# PROC106B_PMIC.net
KiCad netlist of a schematic drawn in Altium Designer
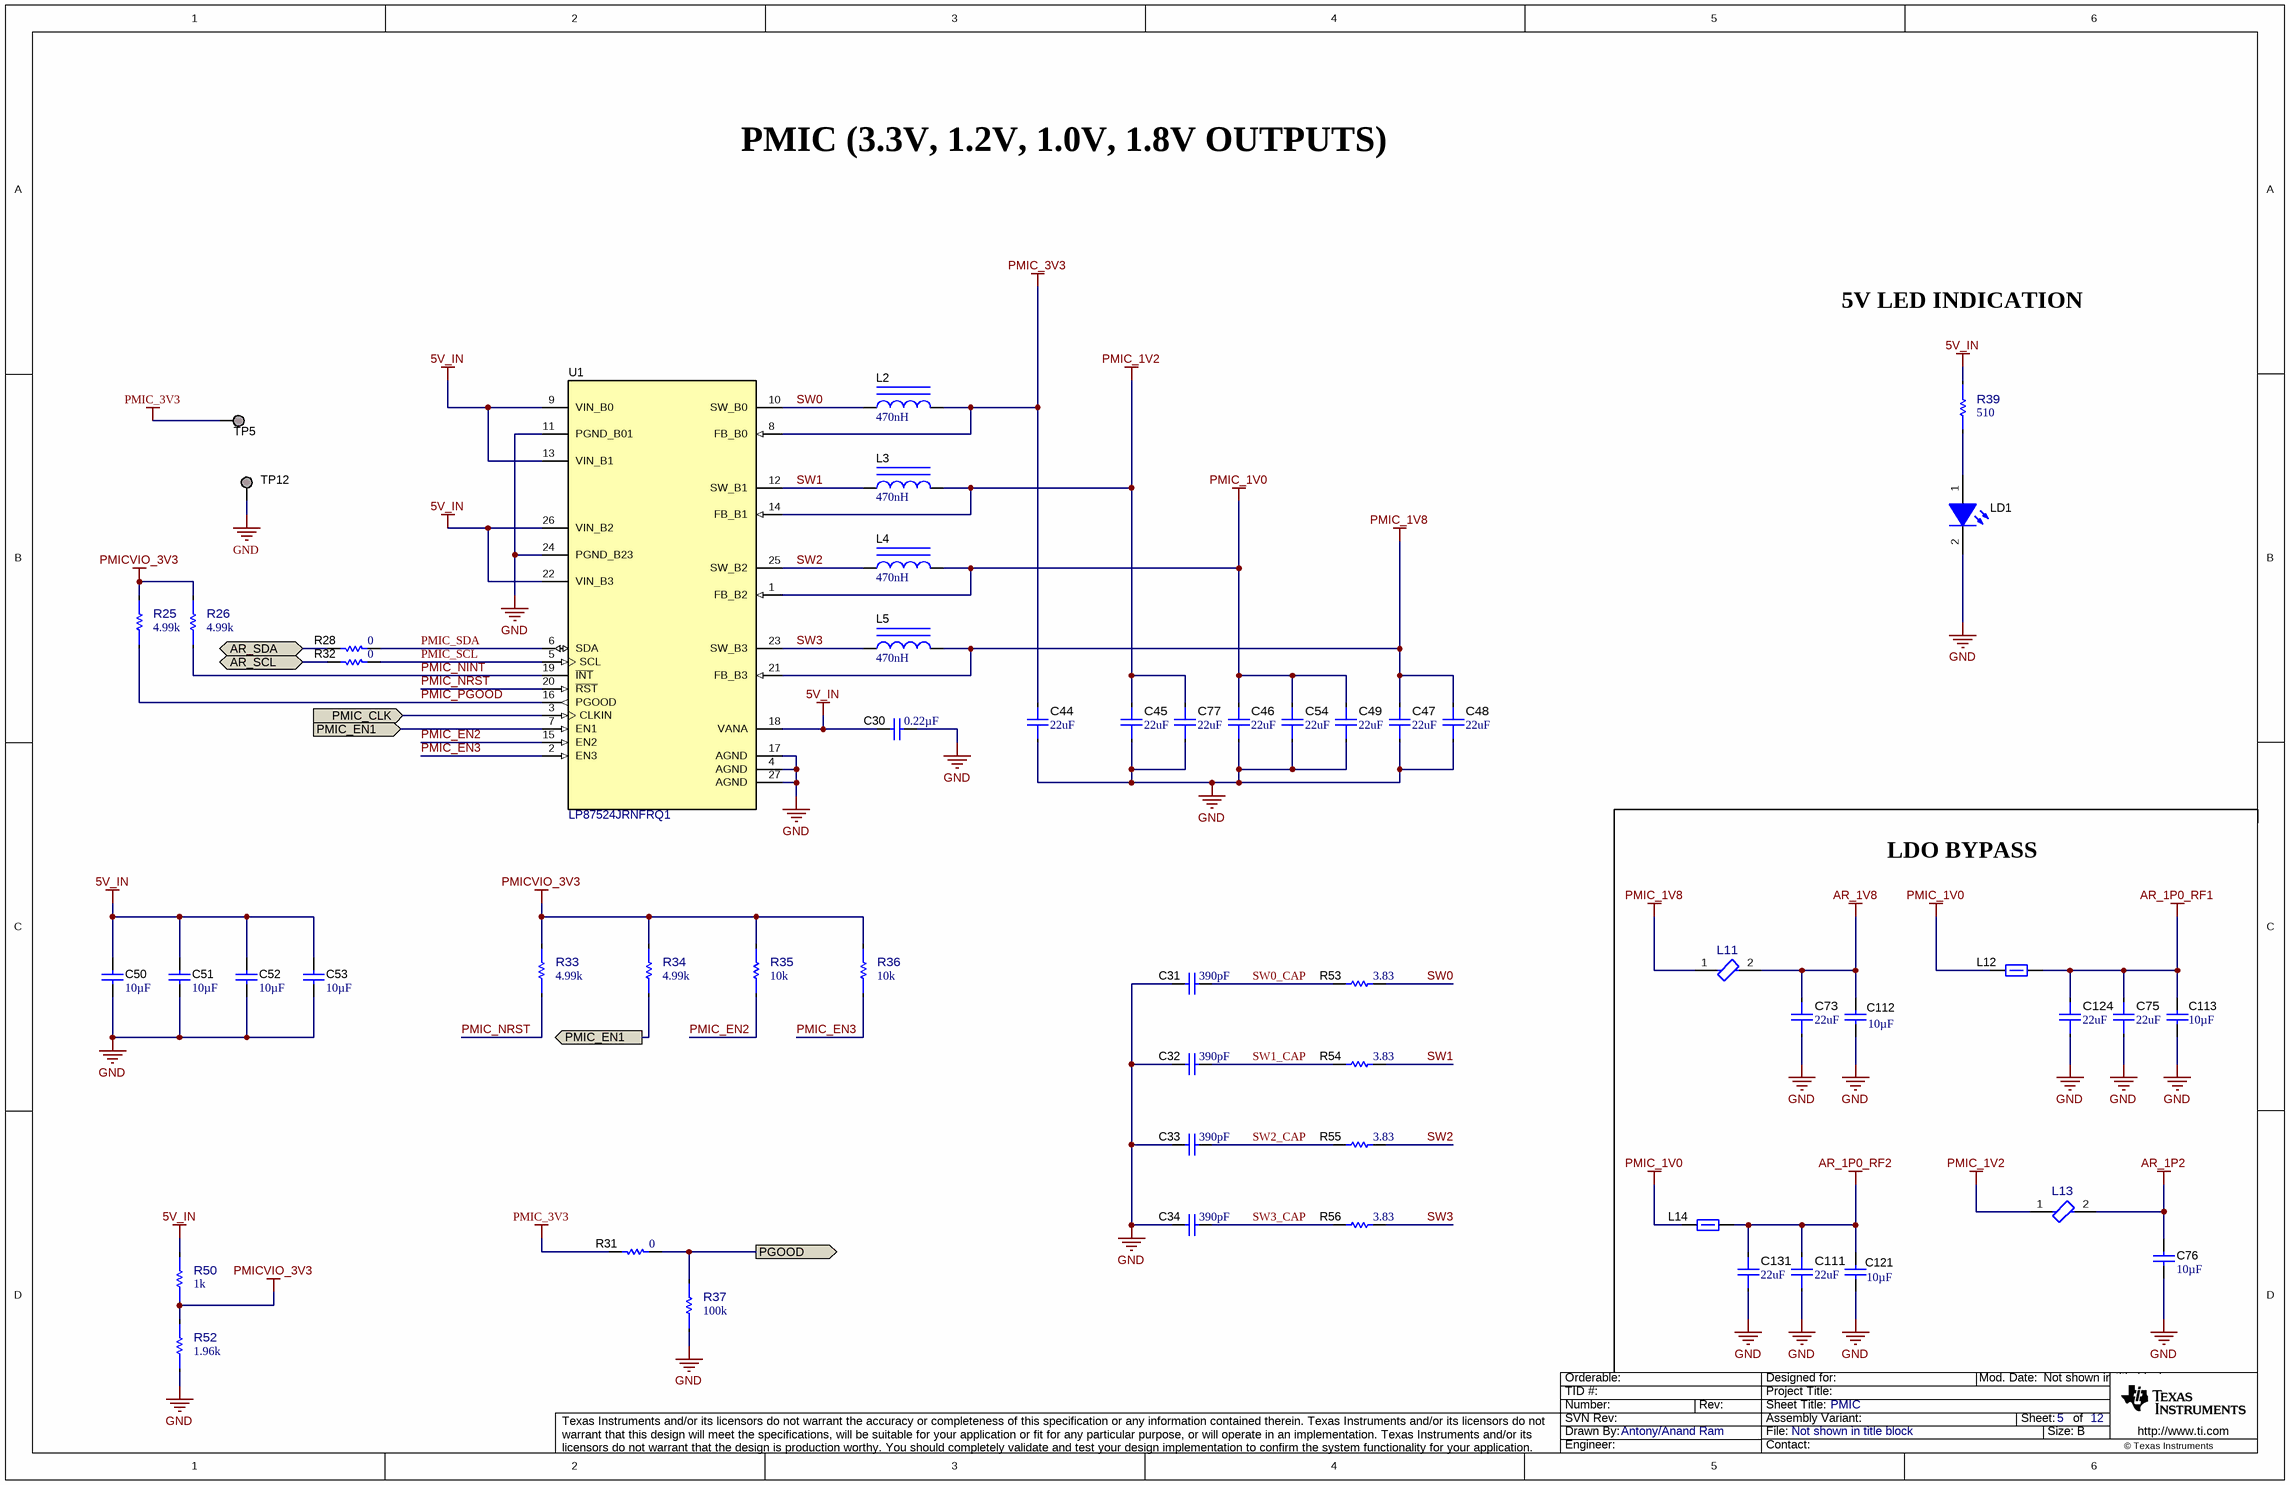
[diagram p0: PROC106B_PMIC.SchDoc]

(export (version "E")
  (design (tool "Eeschema 10.0.6"))
  (components
    (comp (ref "C30")
      (value "GCM155R71C224KE02D")
      (footprint "0402L")
      (description "CAP, CERM, 0.22 µF, 16 V,+/- 10%, X7R, AEC-Q200 Grade 1, 0402")
      (fields (field (name "MANUFACTURER") "MuRata") (field (name "VALUEDISPLAYED") "0.22µF"))
      (libsource (lib "Altium Vault - TI") (part "Capacitor"))
    )
    (comp (ref "C31")
      (value "CGA2B2C0G1H391J050BA")
      (footprint "0402L")
      (description "CAP, CERM, 390 pF, 50 V,+/- 5%, C0G/NP0, AEC-Q200 Grade 1, 0402")
      (fields (field (name "MANUFACTURER") "TDK") (field (name "VALUEDISPLAYED") "390pF"))
      (libsource (lib "Altium Vault - TI") (part "Capacitor"))
    )
    (comp (ref "C32")
      (value "CGA2B2C0G1H391J050BA")
      (footprint "0402L")
      (description "CAP, CERM, 390 pF, 50 V,+/- 5%, C0G/NP0, AEC-Q200 Grade 1, 0402")
      (fields (field (name "MANUFACTURER") "TDK") (field (name "VALUEDISPLAYED") "390pF"))
      (libsource (lib "Altium Vault - TI") (part "Capacitor"))
    )
    (comp (ref "C33")
      (value "CGA2B2C0G1H391J050BA")
      (footprint "0402L")
      (description "CAP, CERM, 390 pF, 50 V,+/- 5%, C0G/NP0, AEC-Q200 Grade 1, 0402")
      (fields (field (name "MANUFACTURER") "TDK") (field (name "VALUEDISPLAYED") "390pF"))
      (libsource (lib "Altium Vault - TI") (part "Capacitor"))
    )
    (comp (ref "C34")
      (value "CGA2B2C0G1H391J050BA")
      (footprint "0402L")
      (description "CAP, CERM, 390 pF, 50 V,+/- 5%, C0G/NP0, AEC-Q200 Grade 1, 0402")
      (fields (field (name "MANUFACTURER") "TDK") (field (name "VALUEDISPLAYED") "390pF"))
      (libsource (lib "Altium Vault - TI") (part "Capacitor"))
    )
    (comp (ref "C44")
      (value "CGA4J1X7T0J226M125AC")
      (footprint "FP-CGA4J1X7T0J226M125AC_0805-MFG")
      (description "22µF ±20% 6.3V Ceramic Capacitor X7T 0805 (2012 Metric)")
      (fields
        (field (name "DIGIKEY PART NUMBER") "445-CGA4J1X7T0J226M125ACCT-ND")
        (field (name "MOUSER PART NUMBER") "810-CGA4J1X7T0J226M1")
        (field (name "VALUEDISPLAYED") "22uF")
      )
      (libsource (lib "Altium Vault - TI") (part "SYM-CGA4J1X7T0J226M125AC"))
    )
    (comp (ref "C45")
      (value "CGA4J1X7T0J226M125AC")
      (footprint "FP-CGA4J1X7T0J226M125AC_0805-MFG")
      (description "22µF ±20% 6.3V Ceramic Capacitor X7T 0805 (2012 Metric)")
      (fields
        (field (name "DIGIKEY PART NUMBER") "445-CGA4J1X7T0J226M125ACCT-ND")
        (field (name "MOUSER PART NUMBER") "810-CGA4J1X7T0J226M1")
        (field (name "VALUEDISPLAYED") "22uF")
      )
      (libsource (lib "Altium Vault - TI") (part "SYM-CGA4J1X7T0J226M125AC"))
    )
    (comp (ref "C46")
      (value "CGA4J1X7T0J226M125AC")
      (footprint "FP-CGA4J1X7T0J226M125AC_0805-MFG")
      (description "22µF ±20% 6.3V Ceramic Capacitor X7T 0805 (2012 Metric)")
      (fields
        (field (name "DIGIKEY PART NUMBER") "445-CGA4J1X7T0J226M125ACCT-ND")
        (field (name "MOUSER PART NUMBER") "810-CGA4J1X7T0J226M1")
        (field (name "VALUEDISPLAYED") "22uF")
      )
      (libsource (lib "Altium Vault - TI") (part "SYM-CGA4J1X7T0J226M125AC"))
    )
    (comp (ref "C47")
      (value "CGA4J1X7T0J226M125AC")
      (footprint "FP-CGA4J1X7T0J226M125AC_0805-MFG")
      (description "22µF ±20% 6.3V Ceramic Capacitor X7T 0805 (2012 Metric)")
      (fields
        (field (name "DIGIKEY PART NUMBER") "445-CGA4J1X7T0J226M125ACCT-ND")
        (field (name "MOUSER PART NUMBER") "810-CGA4J1X7T0J226M1")
        (field (name "VALUEDISPLAYED") "22uF")
      )
      (libsource (lib "Altium Vault - TI") (part "SYM-CGA4J1X7T0J226M125AC"))
    )
    (comp (ref "C48")
      (value "CGA4J1X7T0J226M125AC")
      (footprint "FP-CGA4J1X7T0J226M125AC_0805-MFG")
      (description "22µF ±20% 6.3V Ceramic Capacitor X7T 0805 (2012 Metric)")
      (fields
        (field (name "DIGIKEY PART NUMBER") "445-CGA4J1X7T0J226M125ACCT-ND")
        (field (name "MOUSER PART NUMBER") "810-CGA4J1X7T0J226M1")
        (field (name "VALUEDISPLAYED") "22uF")
      )
      (libsource (lib "Altium Vault - TI") (part "SYM-CGA4J1X7T0J226M125AC"))
    )
    (comp (ref "C49")
      (value "CGA4J1X7T0J226M125AC")
      (footprint "FP-CGA4J1X7T0J226M125AC_0805-MFG")
      (description "22µF ±20% 6.3V Ceramic Capacitor X7T 0805 (2012 Metric)")
      (fields
        (field (name "DIGIKEY PART NUMBER") "445-CGA4J1X7T0J226M125ACCT-ND")
        (field (name "MOUSER PART NUMBER") "810-CGA4J1X7T0J226M1")
        (field (name "VALUEDISPLAYED") "22uF")
      )
      (libsource (lib "Altium Vault - TI") (part "SYM-CGA4J1X7T0J226M125AC"))
    )
    (comp (ref "C50")
      (value "GCM21BR71A106KE22L")
      (footprint "0805_HV1")
      (description "CAP, CERM, 10 uF, 10 V, +/- 10%, X7R, 0805")
      (fields
        (field (name "CAP_F") "10µF")
        (field (name "MANUFACTURER") "MuRata")
        (field (name "PUBLISHER") "Texas Instruments")
      )
      (libsource (lib "Altium Vault - TI") (part "Capacitor"))
    )
    (comp (ref "C51")
      (value "GCM21BR71A106KE22L")
      (footprint "0805_HV1")
      (description "CAP, CERM, 10 uF, 10 V, +/- 10%, X7R, 0805")
      (fields
        (field (name "CAP_F") "10µF")
        (field (name "MANUFACTURER") "MuRata")
        (field (name "PUBLISHER") "Texas Instruments")
      )
      (libsource (lib "Altium Vault - TI") (part "Capacitor"))
    )
    (comp (ref "C52")
      (value "GCM21BR71A106KE22L")
      (footprint "0805_HV1")
      (description "CAP, CERM, 10 uF, 10 V, +/- 10%, X7R, 0805")
      (fields
        (field (name "CAP_F") "10µF")
        (field (name "MANUFACTURER") "MuRata")
        (field (name "PUBLISHER") "Texas Instruments")
      )
      (libsource (lib "Altium Vault - TI") (part "Capacitor"))
    )
    (comp (ref "C53")
      (value "GCM21BR71A106KE22L")
      (footprint "0805_HV1")
      (description "CAP, CERM, 10 uF, 10 V, +/- 10%, X7R, 0805")
      (fields
        (field (name "CAP_F") "10µF")
        (field (name "MANUFACTURER") "MuRata")
        (field (name "PUBLISHER") "Texas Instruments")
      )
      (libsource (lib "Altium Vault - TI") (part "Capacitor"))
    )
    (comp (ref "C54")
      (value "CGA4J1X7T0J226M125AC")
      (footprint "FP-CGA4J1X7T0J226M125AC_0805-MFG")
      (description "22µF ±20% 6.3V Ceramic Capacitor X7T 0805 (2012 Metric)")
      (fields
        (field (name "DIGIKEY PART NUMBER") "445-CGA4J1X7T0J226M125ACCT-ND")
        (field (name "MOUSER PART NUMBER") "810-CGA4J1X7T0J226M1")
        (field (name "VALUEDISPLAYED") "22uF")
      )
      (libsource (lib "Altium Vault - TI") (part "SYM-CGA4J1X7T0J226M125AC"))
    )
    (comp (ref "C73")
      (value "CGA4J1X7T0J226M125AC")
      (footprint "FP-CGA4J1X7T0J226M125AC_0805-MFG")
      (description "22µF ±20% 6.3V Ceramic Capacitor X7T 0805 (2012 Metric)")
      (fields
        (field (name "DIGIKEY PART NUMBER") "445-CGA4J1X7T0J226M125ACCT-ND")
        (field (name "MOUSER PART NUMBER") "810-CGA4J1X7T0J226M1")
        (field (name "VALUEDISPLAYED") "22uF")
      )
      (libsource (lib "Altium Vault - TI") (part "SYM-CGA4J1X7T0J226M125AC"))
    )
    (comp (ref "C75")
      (value "CGA4J1X7T0J226M125AC")
      (footprint "FP-CGA4J1X7T0J226M125AC_0805-MFG")
      (description "22µF ±20% 6.3V Ceramic Capacitor X7T 0805 (2012 Metric)")
      (fields
        (field (name "DIGIKEY PART NUMBER") "445-CGA4J1X7T0J226M125ACCT-ND")
        (field (name "MOUSER PART NUMBER") "810-CGA4J1X7T0J226M1")
        (field (name "VALUEDISPLAYED") "22uF")
      )
      (libsource (lib "Altium Vault - TI") (part "SYM-CGA4J1X7T0J226M125AC"))
    )
    (comp (ref "C76")
      (value "GCM21BR71A106KE22L")
      (footprint "0805L")
      (description "CAP, CERM, 10 uF, 10 V, +/- 10%, X7R, 0805")
      (fields
        (field (name "CAP_F") "10µF")
        (field (name "MANUFACTURER") "MuRata")
        (field (name "PUBLISHER") "Texas Instruments")
      )
      (libsource (lib "Altium Vault - TI") (part "Capacitor"))
    )
    (comp (ref "C77")
      (value "CGA4J1X7T0J226M125AC")
      (footprint "FP-CGA4J1X7T0J226M125AC_0805-MFG")
      (description "22µF ±20% 6.3V Ceramic Capacitor X7T 0805 (2012 Metric)")
      (fields
        (field (name "DIGIKEY PART NUMBER") "445-CGA4J1X7T0J226M125ACCT-ND")
        (field (name "MOUSER PART NUMBER") "810-CGA4J1X7T0J226M1")
        (field (name "VALUEDISPLAYED") "22uF")
      )
      (libsource (lib "Altium Vault - TI") (part "SYM-CGA4J1X7T0J226M125AC"))
    )
    (comp (ref "C111")
      (value "CGA4J1X7T0J226M125AC")
      (footprint "FP-CGA4J1X7T0J226M125AC_0805-MFG")
      (description "22µF ±20% 6.3V Ceramic Capacitor X7T 0805 (2012 Metric)")
      (fields
        (field (name "DIGIKEY PART NUMBER") "445-CGA4J1X7T0J226M125ACCT-ND")
        (field (name "MOUSER PART NUMBER") "810-CGA4J1X7T0J226M1")
        (field (name "VALUEDISPLAYED") "22uF")
      )
      (libsource (lib "Altium Vault - TI") (part "SYM-CGA4J1X7T0J226M125AC"))
    )
    (comp (ref "C112")
      (value "GCM21BR71A106KE22L")
      (footprint "0805L")
      (description "CAP, CERM, 10 uF, 10 V, +/- 10%, X7R, 0805")
      (fields
        (field (name "CAP_F") "10µF")
        (field (name "MANUFACTURER") "MuRata")
        (field (name "PUBLISHER") "Texas Instruments")
      )
      (libsource (lib "Altium Vault - TI") (part "Capacitor"))
    )
    (comp (ref "C113")
      (value "GCM21BR71A106KE22L")
      (footprint "0805L")
      (description "CAP, CERM, 10 uF, 10 V, +/- 10%, X7R, 0805")
      (fields
        (field (name "CAP_F") "10µF")
        (field (name "MANUFACTURER") "MuRata")
        (field (name "PUBLISHER") "Texas Instruments")
      )
      (libsource (lib "Altium Vault - TI") (part "Capacitor"))
    )
    (comp (ref "C121")
      (value "GCM21BR71A106KE22L")
      (footprint "0805L")
      (description "CAP, CERM, 10 uF, 10 V, +/- 10%, X7R, 0805")
      (fields
        (field (name "CAP_F") "10µF")
        (field (name "MANUFACTURER") "MuRata")
        (field (name "PUBLISHER") "Texas Instruments")
      )
      (libsource (lib "Altium Vault - TI") (part "Capacitor"))
    )
    (comp (ref "C124")
      (value "CGA4J1X7T0J226M125AC")
      (footprint "FP-CGA4J1X7T0J226M125AC_0805-MFG")
      (description "22µF ±20% 6.3V Ceramic Capacitor X7T 0805 (2012 Metric)")
      (fields
        (field (name "DIGIKEY PART NUMBER") "445-CGA4J1X7T0J226M125ACCT-ND")
        (field (name "MOUSER PART NUMBER") "810-CGA4J1X7T0J226M1")
        (field (name "VALUEDISPLAYED") "22uF")
      )
      (libsource (lib "Altium Vault - TI") (part "SYM-CGA4J1X7T0J226M125AC"))
    )
    (comp (ref "C131")
      (value "CGA4J1X7T0J226M125AC")
      (footprint "FP-CGA4J1X7T0J226M125AC_0805-MFG")
      (description "22µF ±20% 6.3V Ceramic Capacitor X7T 0805 (2012 Metric)")
      (fields
        (field (name "DIGIKEY PART NUMBER") "445-CGA4J1X7T0J226M125ACCT-ND")
        (field (name "MOUSER PART NUMBER") "810-CGA4J1X7T0J226M1")
        (field (name "VALUEDISPLAYED") "22uF")
      )
      (libsource (lib "Altium Vault - TI") (part "SYM-CGA4J1X7T0J226M125AC"))
    )
    (comp (ref "L2")
      (value "DFE252012PD-R47M")
      (footprint "DFE252012P")
      (description "Inductor, Shielded, 470 nH, 4.7 A, 0.021 ohm, SMD")
      (fields
        (field (name "MANUFACTURER") "MuRata Toko")
        (field (name "VALUEDISPLAYED") "470nH")
        (field (name "PUBLISHER") "Texas Instruments")
      )
      (libsource (lib "Altium Vault - TI") (part "Inductor_Iron"))
    )
    (comp (ref "L3")
      (value "DFE252012PD-R47M")
      (footprint "DFE252012P")
      (description "Inductor, Shielded, 470 nH, 4.7 A, 0.021 ohm, SMD")
      (fields
        (field (name "MANUFACTURER") "MuRata Toko")
        (field (name "VALUEDISPLAYED") "470nH")
        (field (name "PUBLISHER") "Texas Instruments")
      )
      (libsource (lib "Altium Vault - TI") (part "Inductor_Iron"))
    )
    (comp (ref "L4")
      (value "DFE252012PD-R47M")
      (footprint "DFE252012P")
      (description "Inductor, Shielded, 470 nH, 4.7 A, 0.021 ohm, SMD")
      (fields
        (field (name "MANUFACTURER") "MuRata Toko")
        (field (name "VALUEDISPLAYED") "470nH")
        (field (name "PUBLISHER") "Texas Instruments")
      )
      (libsource (lib "Altium Vault - TI") (part "Inductor_Iron"))
    )
    (comp (ref "L5")
      (value "DFE252012PD-R47M")
      (footprint "DFE252012P")
      (description "Inductor, Shielded, 470 nH, 4.7 A, 0.021 ohm, SMD")
      (fields
        (field (name "MANUFACTURER") "MuRata Toko")
        (field (name "VALUEDISPLAYED") "470nH")
        (field (name "PUBLISHER") "Texas Instruments")
      )
      (libsource (lib "Altium Vault - TI") (part "Inductor_Iron"))
    )
    (comp (ref "L11")
      (value "MPZ2012S101ATD25")
      (footprint "FP-MPZ2012S101ATD25_0805-MFG")
      (description "100 Ohms @ 100MHz 1 Power Line Ferrite Bead 0805 (2012 Metric) 4A 20mOhm")
      (fields (field (name "MANUFACTURER") "TDK") (field (name "DIGIKEY PART NUMBER") "445-172903-1-ND"))
      (libsource (lib "Altium Vault - TI") (part "SYM-MPZ2012S101ATD25"))
    )
    (comp (ref "L12")
      (value "BLM18KG121TH1D")
      (footprint "0603_HV")
      (description "Ferrite Bead, 120 ohm @ 100 MHz, 1.9 A, 0603")
      (fields (field (name "MANUFACTURER") "MuRata"))
      (libsource (lib "Altium Vault - TI") (part "Ferrite_Bead"))
    )
    (comp (ref "L13")
      (value "MPZ2012S101ATD25")
      (footprint "FP-MPZ2012S101ATD25_0805-MFG")
      (description "100 Ohms @ 100MHz 1 Power Line Ferrite Bead 0805 (2012 Metric) 4A 20mOhm")
      (fields (field (name "MANUFACTURER") "TDK") (field (name "DIGIKEY PART NUMBER") "445-172903-1-ND"))
      (libsource (lib "Altium Vault - TI") (part "SYM-MPZ2012S101ATD25"))
    )
    (comp (ref "L14")
      (value "BLM18KG121TH1D")
      (footprint "0603_HV")
      (description "Ferrite Bead, 120 ohm @ 100 MHz, 1.9 A, 0603")
      (fields (field (name "MANUFACTURER") "MuRata"))
      (libsource (lib "Altium Vault - TI") (part "Ferrite_Bead"))
    )
    (comp (ref "LD1")
      (value "APHHS1005CGCK")
      (footprint "APHHS1005_Green")
      (description "LED, Green, SMD")
      (fields (field (name "MANUFACTURER") "Kingbright"))
      (libsource (lib "Altium Vault - TI") (part "LED"))
    )
    (comp (ref "R25")
      (value "4.99k")
      (footprint "FP-ERJ-1GNF4991C_0201-IPC_C")
      (description "4.99 kOhms ±1% 0.05W, 1/20W Chip Resistor 0201 (0603 Metric) Automotive AEC-Q200 Thick Film")
      (fields
        (field (name "MANUFACTURER") "Panasonic Electronic Components")
        (field (name "PARTNUMBER") "ERJ-1GNF4991C")
      )
      (libsource (lib "Altium Vault - TI") (part "SYM-ERJ-1GNF4991C"))
    )
    (comp (ref "R26")
      (value "4.99k")
      (footprint "FP-ERJ-1GNF4991C_0201-IPC_C")
      (description "4.99 kOhms ±1% 0.05W, 1/20W Chip Resistor 0201 (0603 Metric) Automotive AEC-Q200 Thick Film")
      (fields
        (field (name "MANUFACTURER") "Panasonic Electronic Components")
        (field (name "PARTNUMBER") "ERJ-1GNF4991C")
      )
      (libsource (lib "Altium Vault - TI") (part "SYM-ERJ-1GNF4991C"))
    )
    (comp (ref "R28")
      (value "ERJ-1GN0R00C")
      (footprint "0201L")
      (description "RES, 0, 5%, .05 W, AEC-Q200 Grade 0, 0201")
      (fields
        (field (name "MANUFACTURER") "Panasonic")
        (field (name "VALUEDISPLAYED") "0")
        (field (name "PUBLISHER") "Texas Instruments")
      )
      (libsource (lib "Altium Vault - TI") (part "Resistor"))
    )
    (comp (ref "R31")
      (value "ERJ-1GN0R00C")
      (footprint "0201L")
      (description "RES, 0, 5%, .05 W, AEC-Q200 Grade 0, 0201")
      (fields
        (field (name "MANUFACTURER") "Panasonic")
        (field (name "VALUEDISPLAYED") "0")
        (field (name "PUBLISHER") "Texas Instruments")
      )
      (libsource (lib "Altium Vault - TI") (part "Resistor"))
    )
    (comp (ref "R32")
      (value "ERJ-1GN0R00C")
      (footprint "0201L")
      (description "RES, 0, 5%, .05 W, AEC-Q200 Grade 0, 0201")
      (fields
        (field (name "MANUFACTURER") "Panasonic")
        (field (name "VALUEDISPLAYED") "0")
        (field (name "PUBLISHER") "Texas Instruments")
      )
      (libsource (lib "Altium Vault - TI") (part "Resistor"))
    )
    (comp (ref "R33")
      (value "4.99k")
      (footprint "FP-ERJ-1GNF4991C_0201-IPC_C")
      (description "4.99 kOhms ±1% 0.05W, 1/20W Chip Resistor 0201 (0603 Metric) Automotive AEC-Q200 Thick Film")
      (fields
        (field (name "MANUFACTURER") "Panasonic Electronic Components")
        (field (name "PARTNUMBER") "ERJ-1GNF4991C")
      )
      (libsource (lib "Altium Vault - TI") (part "SYM-ERJ-1GNF4991C"))
    )
    (comp (ref "R34")
      (value "4.99k")
      (footprint "FP-ERJ-1GNF4991C_0201-IPC_C")
      (description "4.99 kOhms ±1% 0.05W, 1/20W Chip Resistor 0201 (0603 Metric) Automotive AEC-Q200 Thick Film")
      (fields
        (field (name "MANUFACTURER") "Panasonic Electronic Components")
        (field (name "PARTNUMBER") "ERJ-1GNF4991C")
      )
      (libsource (lib "Altium Vault - TI") (part "SYM-ERJ-1GNF4991C"))
    )
    (comp (ref "R35")
      (value "10k")
      (footprint "FP-ERA-1AEB103C_0201-IPC_C")
      (description "RES SMD 10K OHM 0.1% 1/20W 0201")
      (fields (field (name "MANUFACTURER") "Panasonic") (field (name "PARTNUMBER") "ERA-1AEB103C"))
      (libsource (lib "Altium Vault - TI") (part "SYM-ERA-1AEB103C"))
    )
    (comp (ref "R36")
      (value "10k")
      (footprint "FP-ERA-1AEB103C_0201-IPC_C")
      (description "RES SMD 10K OHM 0.1% 1/20W 0201")
      (fields (field (name "MANUFACTURER") "Panasonic") (field (name "PARTNUMBER") "ERA-1AEB103C"))
      (libsource (lib "Altium Vault - TI") (part "SYM-ERA-1AEB103C"))
    )
    (comp (ref "R37")
      (value "100k")
      (footprint "FP-ERJ-1GNF1003C_0201-IPC_C")
      (description "100 kOhms ±1% 0.05W, 1/20W Chip Resistor 0201 (0603 Metric) Automotive AEC-Q200 Thick Film")
      (fields
        (field (name "MANUFACTURER") "Panasonic Electronic Components")
        (field (name "PARTNUMBER") "ERJ-1GNF1003C")
      )
      (libsource (lib "Altium Vault - TI") (part "SYM-ERJ-1GNF1003C"))
    )
    (comp (ref "R39")
      (value "510")
      (footprint "FP-ERJ-1GNJ511C_0201-IPC_C")
      (description "510 Ohms ±5% 0.05W, 1/20W Chip Resistor 0201 (0603 Metric) Automotive AEC-Q200 Thick Film")
      (fields
        (field (name "MANUFACTURER") "Panasonic Electronic Components")
        (field (name "PARTNUMBER") "ERJ-1GNJ511C")
      )
      (libsource (lib "Altium Vault - TI") (part "SYM-ERJ-1GNJ511C"))
    )
    (comp (ref "R50")
      (value "1k")
      (footprint "FP-ERJ-1GNJ102C_0201-IPC_C")
      (description "1 kOhms ±5% 0.05W, 1/20W Chip Resistor 0201 (0603 Metric) Automotive AEC-Q200 Thick Film")
      (fields
        (field (name "MANUFACTURER") "Panasonic Electronic Components")
        (field (name "PARTNUMBER") "ERJ-1GNJ102C")
      )
      (libsource (lib "Altium Vault - TI") (part "SYM-ERJ-1GNJ102C"))
    )
    (comp (ref "R52")
      (value "1.96k")
      (footprint "FP-ERJ-1GNF1961C_0201-IPC_C")
      (description "Res Thick Film 0201 1.96K Ohm 1% 1/20W 200ppm/C Molded SMD T/R")
      (fields (field (name "MANUFACTURER") "Panasonic") (field (name "PARTNUMBER") "ERJ-1GNF1961C"))
      (libsource (lib "Altium Vault - TI") (part "SYM-ERJ-1GNF1961C"))
    )
    (comp (ref "R53")
      (value "CRCW04023R83FKED")
      (footprint "0402L")
      (description "RES, 3.83, 1%, 0.063 W, AEC-Q200 Grade 0, 0402")
      (fields (field (name "MANUFACTURER") "Vishay-Dale") (field (name "VALUEDISPLAYED") "3.83"))
      (libsource (lib "Altium Vault - TI") (part "Resistor"))
    )
    (comp (ref "R54")
      (value "CRCW04023R83FKED")
      (footprint "0402L")
      (description "RES, 3.83, 1%, 0.063 W, AEC-Q200 Grade 0, 0402")
      (fields (field (name "MANUFACTURER") "Vishay-Dale") (field (name "VALUEDISPLAYED") "3.83"))
      (libsource (lib "Altium Vault - TI") (part "Resistor"))
    )
    (comp (ref "R55")
      (value "CRCW04023R83FKED")
      (footprint "0402L")
      (description "RES, 3.83, 1%, 0.063 W, AEC-Q200 Grade 0, 0402")
      (fields (field (name "MANUFACTURER") "Vishay-Dale") (field (name "VALUEDISPLAYED") "3.83"))
      (libsource (lib "Altium Vault - TI") (part "Resistor"))
    )
    (comp (ref "R56")
      (value "CRCW04023R83FKED")
      (footprint "0402L")
      (description "RES, 3.83, 1%, 0.063 W, AEC-Q200 Grade 0, 0402")
      (fields (field (name "MANUFACTURER") "Vishay-Dale") (field (name "VALUEDISPLAYED") "3.83"))
      (libsource (lib "Altium Vault - TI") (part "Resistor"))
    )
    (comp (ref "TP5")
      (value "TESTPOINT")
      (footprint "TP_25MIL-SMT")
      (description "TEST POINT.  No entry in BOM.")
      (libsource (lib "Altium Vault - TI") (part "TESTPOINT"))
    )
    (comp (ref "TP12")
      (value "TESTPOINT")
      (footprint "TP_VIA_060RND040")
      (description "TEST POINT.  No entry in BOM.")
      (libsource (lib "Altium Vault - TI") (part "TESTPOINT"))
    )
    (comp (ref "U1")
      (value "LP87524JRNFRQ1")
      (footprint "RNF0026C")
      (description "4-A + 2.5-A + Two 1.5-A Buck Converters With Integrated Switches, RNF0026C (VQFN-HR-26)")
      (fields
        (field (name "ALTERNATE PARTNUMBER") "LP87524JRNFTQ1")
        (field (name "MANUFACTURER") "Texas Instruments")
      )
      (libsource (lib "Altium Vault - TI") (part "LP87524"))
    )
  )
  (nets
    (net (code "1") (name "/AR_SCL") (class "Default")
      (node (ref "R32") (pin "1") (pinfunction "1_1") (pintype "passive"))
    )
    (net (code "2") (name "/AR_SDA") (class "Default")
      (node (ref "R28") (pin "1") (pinfunction "1_1") (pintype "passive"))
    )
    (net (code "3") (name "/PGOOD") (class "Default")
      (node (ref "R31") (pin "2") (pinfunction "2_2") (pintype "passive"))
      (node (ref "R37") (pin "2") (pinfunction "2_2") (pintype "passive"))
    )
    (net (code "4") (name "/PMIC_CLK") (class "Default")
      (node (ref "U1") (pin "3") (pinfunction "CLKIN_3") (pintype "input"))
    )
    (net (code "5") (name "/PMIC_EN1") (class "Default")
      (node (ref "R34") (pin "1") (pinfunction "1_1") (pintype "passive"))
      (node (ref "U1") (pin "7") (pinfunction "EN1_7") (pintype "input"))
    )
    (net (code "6") (name "/PMIC_EN2") (class "Default")
      (node (ref "R35") (pin "1") (pinfunction "1_1") (pintype "passive"))
      (node (ref "U1") (pin "15") (pinfunction "EN2_15") (pintype "input"))
    )
    (net (code "7") (name "/PMIC_EN3") (class "Default")
      (node (ref "R36") (pin "1") (pinfunction "1_1") (pintype "passive"))
      (node (ref "U1") (pin "2") (pinfunction "EN3_2") (pintype "input"))
    )
    (net (code "8") (name "/PMIC_NINT") (class "Default")
      (node (ref "R26") (pin "1") (pinfunction "1_1") (pintype "passive"))
      (node (ref "U1") (pin "19") (pinfunction "INT_19") (pintype "open_collector"))
    )
    (net (code "9") (name "/PMIC_NRST") (class "Default")
      (node (ref "R33") (pin "1") (pinfunction "1_1") (pintype "passive"))
      (node (ref "U1") (pin "20") (pinfunction "RST_20") (pintype "input"))
    )
    (net (code "10") (name "/PMIC_PGOOD") (class "Default")
      (node (ref "R25") (pin "1") (pinfunction "1_1") (pintype "passive"))
      (node (ref "U1") (pin "16") (pinfunction "PGOOD_16") (pintype "output"))
    )
    (net (code "11") (name "/PMIC_SCL") (class "Default")
      (node (ref "R32") (pin "2") (pinfunction "2_2") (pintype "passive"))
      (node (ref "U1") (pin "5") (pinfunction "SCL_5") (pintype "input"))
    )
    (net (code "12") (name "/PMIC_SDA") (class "Default")
      (node (ref "R28") (pin "2") (pinfunction "2_2") (pintype "passive"))
      (node (ref "U1") (pin "6") (pinfunction "SDA_6") (pintype "bidirectional"))
    )
    (net (code "13") (name "/SW0") (class "Default")
      (node (ref "L2") (pin "2") (pinfunction "2_2") (pintype "passive"))
      (node (ref "R53") (pin "2") (pinfunction "2_2") (pintype "passive"))
      (node (ref "U1") (pin "10") (pinfunction "SW_B0_10") (pintype "power_in"))
    )
    (net (code "14") (name "/SW0_CAP") (class "Default")
      (node (ref "C31") (pin "1") (pinfunction "1_1") (pintype "passive"))
      (node (ref "R53") (pin "1") (pinfunction "1_1") (pintype "passive"))
    )
    (net (code "15") (name "/SW1") (class "Default")
      (node (ref "L3") (pin "2") (pinfunction "2_2") (pintype "passive"))
      (node (ref "R54") (pin "2") (pinfunction "2_2") (pintype "passive"))
      (node (ref "U1") (pin "12") (pinfunction "SW_B1_12") (pintype "power_in"))
    )
    (net (code "16") (name "/SW1_CAP") (class "Default")
      (node (ref "C32") (pin "1") (pinfunction "1_1") (pintype "passive"))
      (node (ref "R54") (pin "1") (pinfunction "1_1") (pintype "passive"))
    )
    (net (code "17") (name "/SW2") (class "Default")
      (node (ref "L4") (pin "2") (pinfunction "2_2") (pintype "passive"))
      (node (ref "R55") (pin "2") (pinfunction "2_2") (pintype "passive"))
      (node (ref "U1") (pin "25") (pinfunction "SW_B2_25") (pintype "power_in"))
    )
    (net (code "18") (name "/SW2_CAP") (class "Default")
      (node (ref "C33") (pin "2") (pinfunction "2_2") (pintype "passive"))
      (node (ref "R55") (pin "1") (pinfunction "1_1") (pintype "passive"))
    )
    (net (code "19") (name "/SW3") (class "Default")
      (node (ref "L5") (pin "2") (pinfunction "2_2") (pintype "passive"))
      (node (ref "R56") (pin "2") (pinfunction "2_2") (pintype "passive"))
      (node (ref "U1") (pin "23") (pinfunction "SW_B3_23") (pintype "power_in"))
    )
    (net (code "20") (name "/SW3_CAP") (class "Default")
      (node (ref "C34") (pin "2") (pinfunction "2_2") (pintype "passive"))
      (node (ref "R56") (pin "1") (pinfunction "1_1") (pintype "passive"))
    )
    (net (code "21") (name "5V_IN") (class "Default")
      (node (ref "C30") (pin "1") (pinfunction "1_1") (pintype "passive"))
      (node (ref "C50") (pin "1") (pinfunction "1_1") (pintype "passive"))
      (node (ref "C51") (pin "1") (pinfunction "1_1") (pintype "passive"))
      (node (ref "C52") (pin "1") (pinfunction "1_1") (pintype "passive"))
      (node (ref "C53") (pin "1") (pinfunction "1_1") (pintype "passive"))
      (node (ref "R39") (pin "1") (pinfunction "1_1") (pintype "passive"))
      (node (ref "R50") (pin "2") (pinfunction "2_2") (pintype "passive"))
      (node (ref "U1") (pin "13") (pinfunction "VIN_B1_13") (pintype "power_in"))
      (node (ref "U1") (pin "18") (pinfunction "VANA_18") (pintype "power_in"))
      (node (ref "U1") (pin "22") (pinfunction "VIN_B3_22") (pintype "power_in"))
      (node (ref "U1") (pin "26") (pinfunction "VIN_B2_26") (pintype "power_in"))
      (node (ref "U1") (pin "9") (pinfunction "VIN_B0_9") (pintype "power_in"))
    )
    (net (code "22") (name "AR_1P0_RF1") (class "Default")
      (node (ref "C113") (pin "1") (pinfunction "1_1") (pintype "passive"))
      (node (ref "C124") (pin "2") (pinfunction "2_2") (pintype "passive"))
      (node (ref "C75") (pin "2") (pinfunction "2_2") (pintype "passive"))
      (node (ref "L12") (pin "2") (pinfunction "2_2") (pintype "passive"))
    )
    (net (code "23") (name "AR_1P0_RF2") (class "Default")
      (node (ref "C111") (pin "2") (pinfunction "2_2") (pintype "passive"))
      (node (ref "C121") (pin "1") (pinfunction "1_1") (pintype "passive"))
      (node (ref "C131") (pin "2") (pinfunction "2_2") (pintype "passive"))
      (node (ref "L14") (pin "2") (pinfunction "2_2") (pintype "passive"))
    )
    (net (code "24") (name "AR_1P2") (class "Default")
      (node (ref "C76") (pin "1") (pinfunction "1_1") (pintype "passive"))
      (node (ref "L13") (pin "2") (pinfunction "2_2") (pintype "passive"))
    )
    (net (code "25") (name "AR_1V8") (class "Default")
      (node (ref "C112") (pin "1") (pinfunction "1_1") (pintype "passive"))
      (node (ref "C73") (pin "2") (pinfunction "2_2") (pintype "passive"))
      (node (ref "L11") (pin "2") (pinfunction "2_2") (pintype "passive"))
    )
    (net (code "26") (name "GND") (class "Default")
      (node (ref "C111") (pin "1") (pinfunction "1_1") (pintype "passive"))
      (node (ref "C112") (pin "2") (pinfunction "2_2") (pintype "passive"))
      (node (ref "C113") (pin "2") (pinfunction "2_2") (pintype "passive"))
      (node (ref "C121") (pin "2") (pinfunction "2_2") (pintype "passive"))
      (node (ref "C124") (pin "1") (pinfunction "1_1") (pintype "passive"))
      (node (ref "C131") (pin "1") (pinfunction "1_1") (pintype "passive"))
      (node (ref "C30") (pin "2") (pinfunction "2_2") (pintype "passive"))
      (node (ref "C31") (pin "2") (pinfunction "2_2") (pintype "passive"))
      (node (ref "C32") (pin "2") (pinfunction "2_2") (pintype "passive"))
      (node (ref "C33") (pin "1") (pinfunction "1_1") (pintype "passive"))
      (node (ref "C34") (pin "1") (pinfunction "1_1") (pintype "passive"))
      (node (ref "C44") (pin "1") (pinfunction "1_1") (pintype "passive"))
      (node (ref "C45") (pin "1") (pinfunction "1_1") (pintype "passive"))
      (node (ref "C46") (pin "1") (pinfunction "1_1") (pintype "passive"))
      (node (ref "C47") (pin "1") (pinfunction "1_1") (pintype "passive"))
      (node (ref "C48") (pin "1") (pinfunction "1_1") (pintype "passive"))
      (node (ref "C49") (pin "1") (pinfunction "1_1") (pintype "passive"))
      (node (ref "C50") (pin "2") (pinfunction "2_2") (pintype "passive"))
      (node (ref "C51") (pin "2") (pinfunction "2_2") (pintype "passive"))
      (node (ref "C52") (pin "2") (pinfunction "2_2") (pintype "passive"))
      (node (ref "C53") (pin "2") (pinfunction "2_2") (pintype "passive"))
      (node (ref "C54") (pin "1") (pinfunction "1_1") (pintype "passive"))
      (node (ref "C73") (pin "1") (pinfunction "1_1") (pintype "passive"))
      (node (ref "C75") (pin "1") (pinfunction "1_1") (pintype "passive"))
      (node (ref "C76") (pin "2") (pinfunction "2_2") (pintype "passive"))
      (node (ref "C77") (pin "1") (pinfunction "1_1") (pintype "passive"))
      (node (ref "LD1") (pin "2") (pinfunction "K_2") (pintype "passive"))
      (node (ref "R37") (pin "1") (pinfunction "1_1") (pintype "passive"))
      (node (ref "R52") (pin "1") (pinfunction "1_1") (pintype "passive"))
      (node (ref "TP12") (pin "1") (pintype "passive"))
      (node (ref "U1") (pin "11") (pinfunction "PGND_B01_11") (pintype "power_in"))
      (node (ref "U1") (pin "17") (pinfunction "AGND_17") (pintype "power_in"))
      (node (ref "U1") (pin "24") (pinfunction "PGND_B23_24") (pintype "power_in"))
      (node (ref "U1") (pin "27") (pinfunction "AGND_27") (pintype "power_in"))
      (node (ref "U1") (pin "4") (pinfunction "AGND_4") (pintype "power_in"))
    )
    (net (code "27") (name "Net-(LD1-A)") (class "Default")
      (node (ref "LD1") (pin "1") (pinfunction "A_1") (pintype "passive"))
      (node (ref "R39") (pin "2") (pinfunction "2_2") (pintype "passive"))
    )
    (net (code "28") (name "PMICVIO_3V3") (class "Default")
      (node (ref "R25") (pin "2") (pinfunction "2_2") (pintype "passive"))
      (node (ref "R26") (pin "2") (pinfunction "2_2") (pintype "passive"))
      (node (ref "R33") (pin "2") (pinfunction "2_2") (pintype "passive"))
      (node (ref "R34") (pin "2") (pinfunction "2_2") (pintype "passive"))
      (node (ref "R35") (pin "2") (pinfunction "2_2") (pintype "passive"))
      (node (ref "R36") (pin "2") (pinfunction "2_2") (pintype "passive"))
      (node (ref "R50") (pin "1") (pinfunction "1_1") (pintype "passive"))
      (node (ref "R52") (pin "2") (pinfunction "2_2") (pintype "passive"))
    )
    (net (code "29") (name "PMIC_1V0") (class "Default")
      (node (ref "C46") (pin "2") (pinfunction "2_2") (pintype "passive"))
      (node (ref "C49") (pin "2") (pinfunction "2_2") (pintype "passive"))
      (node (ref "C54") (pin "2") (pinfunction "2_2") (pintype "passive"))
      (node (ref "L12") (pin "1") (pinfunction "1_1") (pintype "passive"))
      (node (ref "L14") (pin "1") (pinfunction "1_1") (pintype "passive"))
      (node (ref "L4") (pin "1") (pinfunction "1_1") (pintype "passive"))
      (node (ref "U1") (pin "1") (pinfunction "FB_B2_1") (pintype "input"))
    )
    (net (code "30") (name "PMIC_1V2") (class "Default")
      (node (ref "C45") (pin "2") (pinfunction "2_2") (pintype "passive"))
      (node (ref "C77") (pin "2") (pinfunction "2_2") (pintype "passive"))
      (node (ref "L13") (pin "1") (pinfunction "1_1") (pintype "passive"))
      (node (ref "L3") (pin "1") (pinfunction "1_1") (pintype "passive"))
      (node (ref "U1") (pin "14") (pinfunction "FB_B1_14") (pintype "input"))
    )
    (net (code "31") (name "PMIC_1V8") (class "Default")
      (node (ref "C47") (pin "2") (pinfunction "2_2") (pintype "passive"))
      (node (ref "C48") (pin "2") (pinfunction "2_2") (pintype "passive"))
      (node (ref "L11") (pin "1") (pinfunction "1_1") (pintype "passive"))
      (node (ref "L5") (pin "1") (pinfunction "1_1") (pintype "passive"))
      (node (ref "U1") (pin "21") (pinfunction "FB_B3_21") (pintype "input"))
    )
    (net (code "32") (name "PMIC_3V3") (class "Default")
      (node (ref "C44") (pin "2") (pinfunction "2_2") (pintype "passive"))
      (node (ref "L2") (pin "1") (pinfunction "1_1") (pintype "passive"))
      (node (ref "R31") (pin "1") (pinfunction "1_1") (pintype "passive"))
      (node (ref "TP5") (pin "1") (pintype "passive"))
      (node (ref "U1") (pin "8") (pinfunction "FB_B0_8") (pintype "input"))
    )
  )
)
